# ModuleCarrier-ISM4334X-M4G-L44.net
KiCad netlist of a schematic drawn in EAGLE
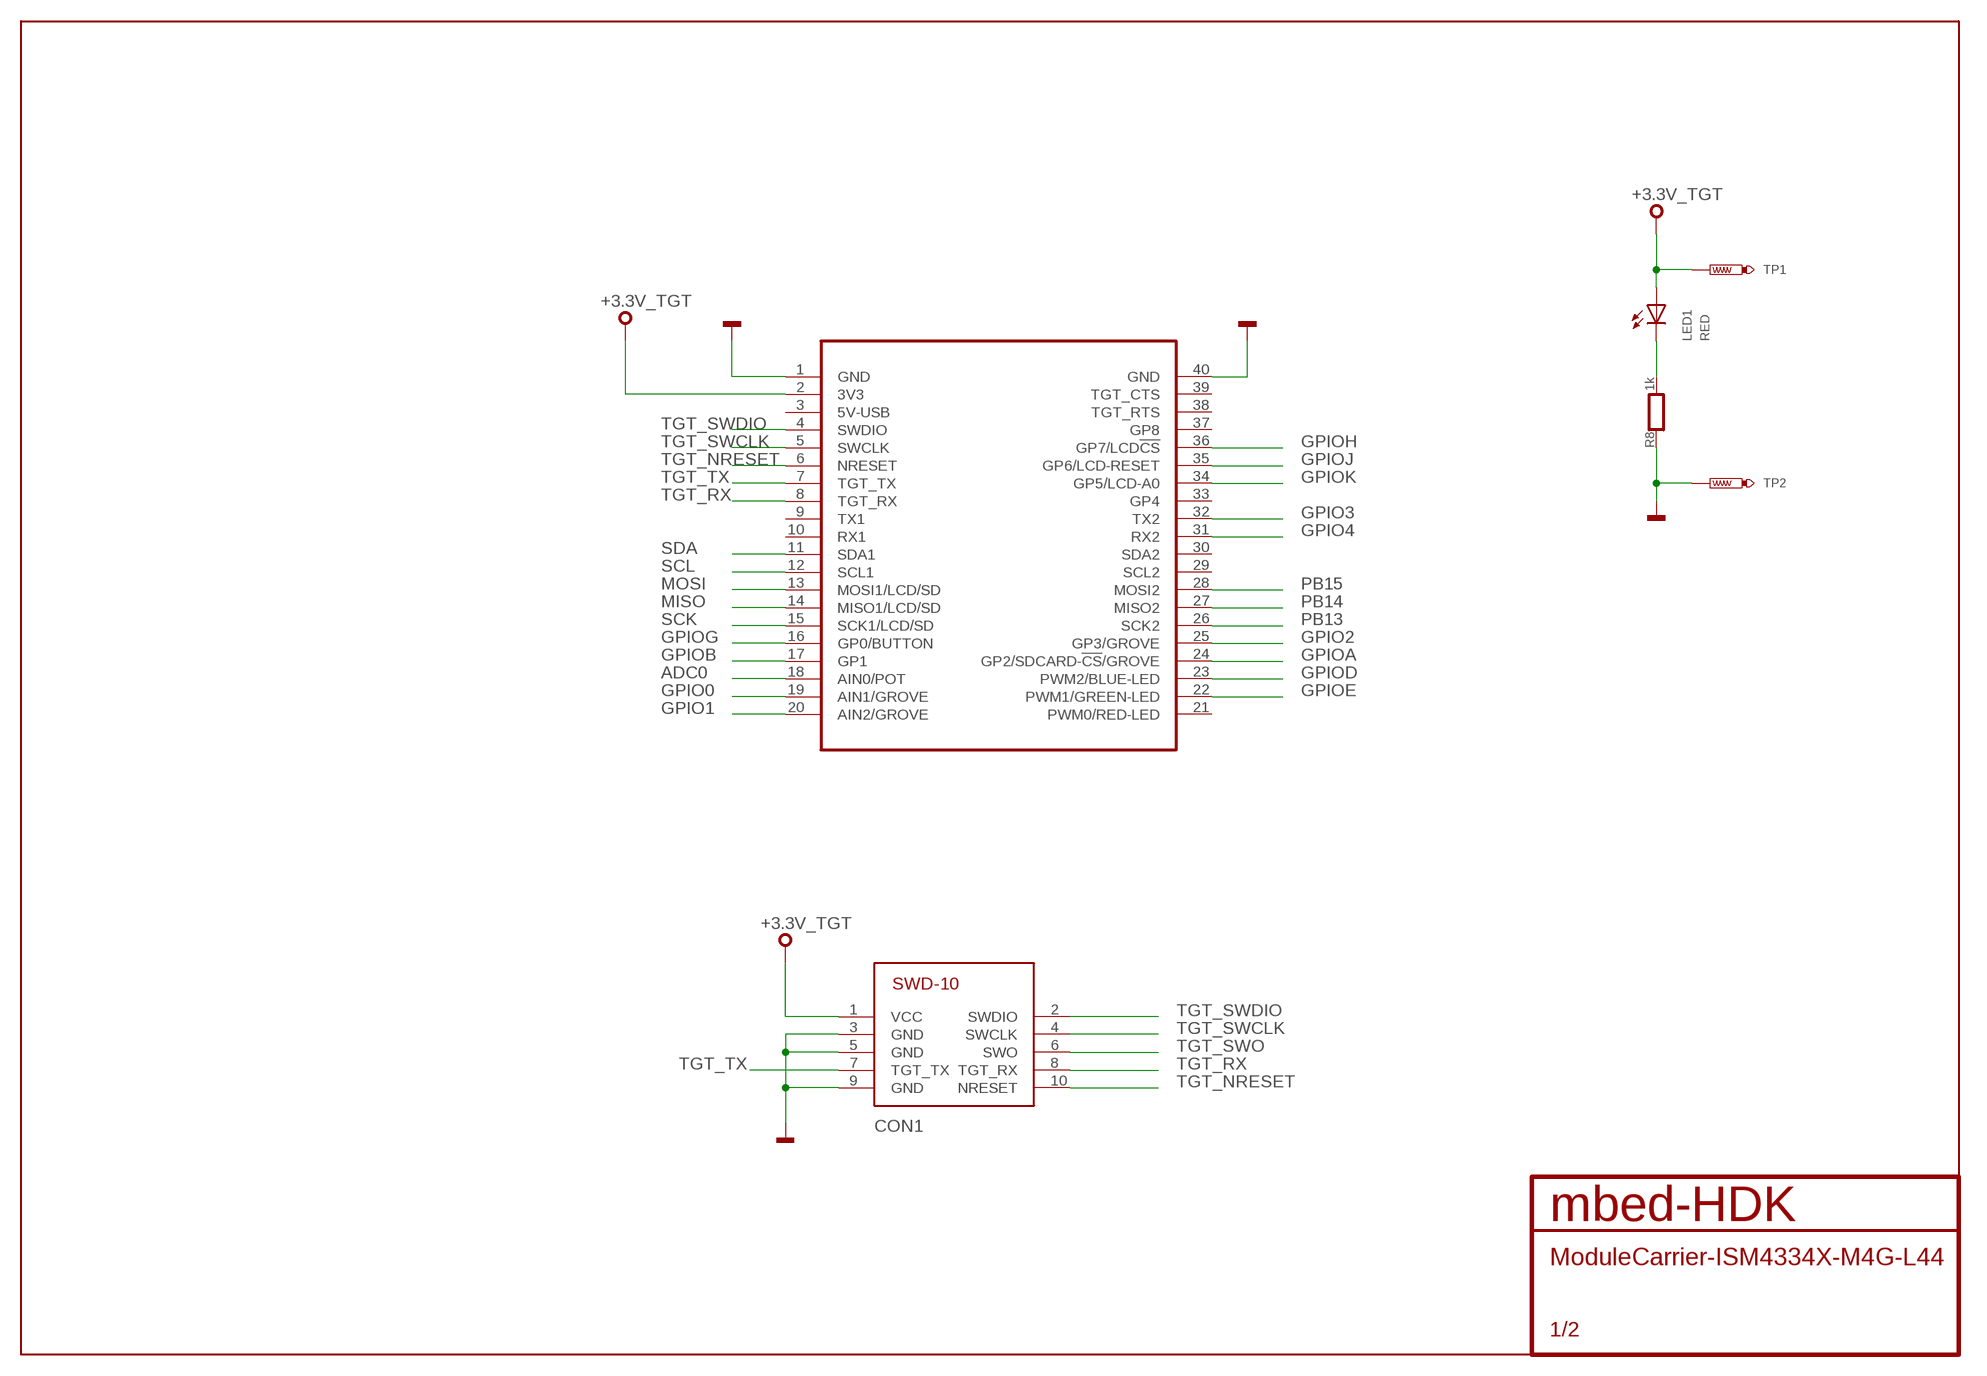
[diagram p0: schematic, sheet 1]
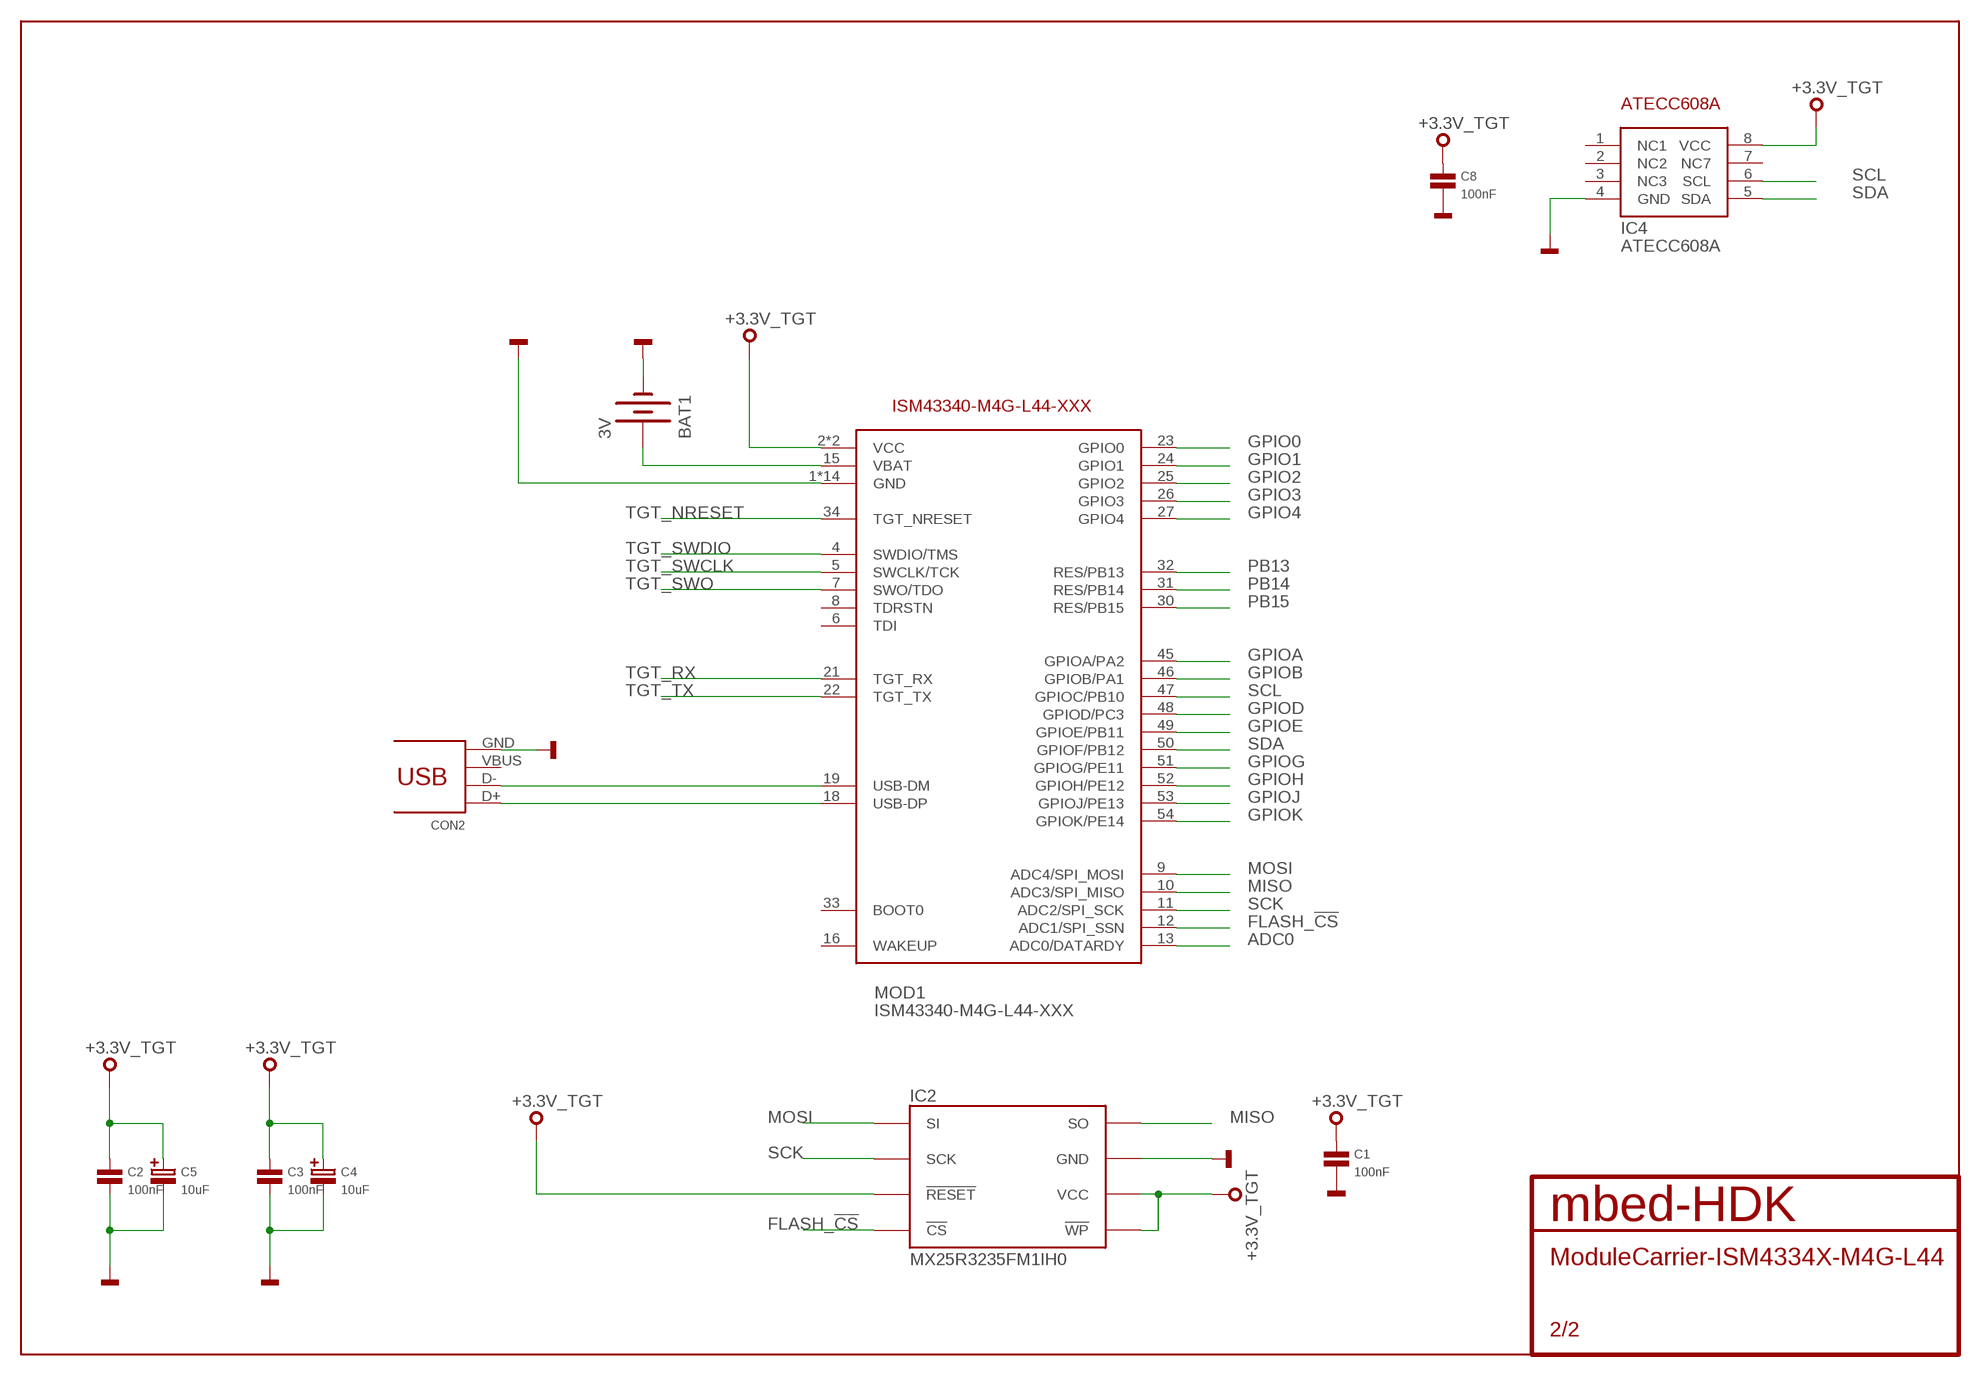
[diagram p1: schematic, sheet 2]

(export (version "E")
  (design (tool "Eeschema 10.0.6"))
  (components
    (comp (ref "BAT1")
      (value "3V")
      (footprint "eagle-import:BATTCON_12MM")
      (libsource (lib "eagle-import") (part "BATTERY12MM"))
    )
    (comp (ref "C1")
      (value "100nF")
      (footprint "eagle-import:0603")
      (libsource (lib "eagle-import") (part "CAPACITOR0603"))
    )
    (comp (ref "C2")
      (value "100nF")
      (footprint "eagle-import:0603")
      (libsource (lib "eagle-import") (part "CAPACITOR0603"))
    )
    (comp (ref "C3")
      (value "100nF")
      (footprint "eagle-import:0603")
      (libsource (lib "eagle-import") (part "CAPACITOR0603"))
    )
    (comp (ref "C4")
      (value "10uF")
      (footprint "eagle-import:SMC_B")
      (fields (field (name "MF") "Kemet"))
      (libsource (lib "eagle-import") (part "CAPACITOR-POLARISEDB"))
    )
    (comp (ref "C5")
      (value "10uF")
      (footprint "eagle-import:SMC_B")
      (fields (field (name "MF") "Kemet"))
      (libsource (lib "eagle-import") (part "CAPACITOR-POLARISEDB"))
    )
    (comp (ref "C8")
      (value "100nF")
      (footprint "eagle-import:0603")
      (libsource (lib "eagle-import") (part "CAPACITOR0603"))
    )
    (comp (ref "CON2")
      (value "10033526-N3212MLF")
      (footprint "eagle-import:USB-MINI-B-H")
      (fields (field (name "MF") "Amphenol FCI"))
      (libsource (lib "eagle-import") (part "10033526-N3212MLF"))
    )
    (comp (ref "IC2")
      (value "MX25R3235FM1IH0")
      (footprint "eagle-import:SO8")
      (fields (field (name "MF") "Macronix"))
      (libsource (lib "eagle-import") (part "MX25R3235FM1IH0"))
    )
    (comp (ref "IC4")
      (value "ATECC608A")
      (footprint "eagle-import:SO8")
      (libsource (lib "eagle-import") (part "ATECC608A"))
    )
    (comp (ref "MOD1")
      (value "ISM43340-M4G-L44-XXX")
      (footprint "eagle-import:ISM43340-M4G-L44-XXX")
      (libsource (lib "eagle-import") (part "ISM43340-M4G-L44-XXX"))
    )
    (comp (ref "CON1")
      (value "SWD-10/TC2050_SMD")
      (footprint "eagle-import:FTSH-105-02")
      (libsource (lib "eagle-import") (part "SWD-10/TC2050_SMD"))
    )
    (comp (ref "LED1")
      (value "RED")
      (footprint "eagle-import:CHIPLED_0603")
      (fields (field (name "MF") "Wurth Electronics Inc"))
      (libsource (lib "eagle-import") (part "SMD_LED0603"))
    )
    (comp (ref "MOD2")
      (value "MODULE_DAUGHTER")
      (footprint "eagle-import:MODULE_DAUGHTER")
      (libsource (lib "eagle-import") (part "MODULE_DAUGHTER"))
    )
    (comp (ref "R8")
      (value "1k")
      (footprint "eagle-import:0603")
      (libsource (lib "eagle-import") (part "RESISTOR0603"))
    )
    (comp (ref "TP1")
      (value "TEST-POINT-50R-PTH")
      (footprint "eagle-import:TP50-PTH")
      (libsource (lib "eagle-import") (part "TEST-POINT-50R-PTH"))
    )
    (comp (ref "TP2")
      (value "TEST-POINT-50R-PTH")
      (footprint "eagle-import:TP50-PTH")
      (libsource (lib "eagle-import") (part "TEST-POINT-50R-PTH"))
    )
  )
  (nets
    (net (code "1") (name "+3.3V_TGT") (class "Default")
      (node (ref "C1") (pin "1") (pinfunction "P$1_1") (pintype "passive"))
      (node (ref "C2") (pin "1") (pinfunction "P$1_1") (pintype "passive"))
      (node (ref "C3") (pin "1") (pinfunction "P$1_1") (pintype "passive"))
      (node (ref "C4") (pin "+") (pinfunction "+_+") (pintype "passive"))
      (node (ref "C5") (pin "+") (pinfunction "+_+") (pintype "passive"))
      (node (ref "C8") (pin "1") (pinfunction "P$1_1") (pintype "passive"))
      (node (ref "CON1") (pin "1") (pinfunction "VCC_1") (pintype "bidirectional"))
      (node (ref "IC2") (pin "3") (pinfunction "~{WP}_3") (pintype "bidirectional"))
      (node (ref "IC2") (pin "7") (pinfunction "~{RESET}_7") (pintype "bidirectional"))
      (node (ref "IC2") (pin "8") (pinfunction "VCC_8") (pintype "bidirectional"))
      (node (ref "IC4") (pin "8") (pinfunction "VCC_8") (pintype "bidirectional"))
      (node (ref "LED1") (pin "A") (pinfunction "A_A") (pintype "passive"))
      (node (ref "MOD1") (pin "14") (pinfunction "VCC_14") (pintype "bidirectional"))
      (node (ref "MOD1") (pin "2") (pinfunction "VCC_2") (pintype "bidirectional"))
      (node (ref "MOD2") (pin "2") (pinfunction "3V3_2") (pintype "bidirectional"))
      (node (ref "TP1") (pin "TP") (pinfunction "TP_TP") (pintype "input"))
    )
    (net (code "2") (name "ADC0") (class "Default")
      (node (ref "MOD1") (pin "13") (pinfunction "ADC0/DATARDY_13") (pintype "bidirectional"))
      (node (ref "MOD2") (pin "18") (pinfunction "AIN0/POT_18") (pintype "bidirectional"))
    )
    (net (code "3") (name "FLASH_~{CS}") (class "Default")
      (node (ref "IC2") (pin "1") (pinfunction "~{CS}_1") (pintype "bidirectional"))
      (node (ref "MOD1") (pin "12") (pinfunction "ADC1/SPI_SSN_12") (pintype "bidirectional"))
    )
    (net (code "4") (name "GND") (class "Default")
      (node (ref "BAT1") (pin "GND") (pinfunction "-_GND") (pintype "power_in"))
      (node (ref "C1") (pin "2") (pinfunction "P$2_2") (pintype "passive"))
      (node (ref "C2") (pin "2") (pinfunction "P$2_2") (pintype "passive"))
      (node (ref "C3") (pin "2") (pinfunction "P$2_2") (pintype "passive"))
      (node (ref "C4") (pin "-") (pinfunction "-_-") (pintype "passive"))
      (node (ref "C5") (pin "-") (pinfunction "-_-") (pintype "passive"))
      (node (ref "C8") (pin "2") (pinfunction "P$2_2") (pintype "passive"))
      (node (ref "CON1") (pin "3") (pinfunction "GND_3") (pintype "bidirectional"))
      (node (ref "CON1") (pin "5") (pinfunction "GND_5") (pintype "bidirectional"))
      (node (ref "CON1") (pin "9") (pinfunction "GND_9") (pintype "bidirectional"))
      (node (ref "CON2") (pin "GND") (pinfunction "GND_GND") (pintype "bidirectional"))
      (node (ref "IC2") (pin "4") (pinfunction "GND_4") (pintype "bidirectional"))
      (node (ref "IC4") (pin "4") (pinfunction "GND_4") (pintype "bidirectional"))
      (node (ref "MOD1") (pin "1") (pinfunction "GND_1") (pintype "bidirectional"))
      (node (ref "MOD1") (pin "17") (pinfunction "GND_17") (pintype "bidirectional"))
      (node (ref "MOD1") (pin "20") (pinfunction "GND_20") (pintype "bidirectional"))
      (node (ref "MOD1") (pin "3") (pinfunction "GND_3") (pintype "bidirectional"))
      (node (ref "MOD1") (pin "35") (pinfunction "GND_35") (pintype "bidirectional"))
      (node (ref "MOD1") (pin "36") (pinfunction "GND_36") (pintype "bidirectional"))
      (node (ref "MOD1") (pin "37") (pinfunction "GND_37") (pintype "bidirectional"))
      (node (ref "MOD1") (pin "38") (pinfunction "GND_38") (pintype "bidirectional"))
      (node (ref "MOD1") (pin "39") (pinfunction "GND_39") (pintype "bidirectional"))
      (node (ref "MOD1") (pin "40") (pinfunction "GND_40") (pintype "bidirectional"))
      (node (ref "MOD1") (pin "41") (pinfunction "GND_41") (pintype "bidirectional"))
      (node (ref "MOD1") (pin "42") (pinfunction "GND_42") (pintype "bidirectional"))
      (node (ref "MOD1") (pin "43") (pinfunction "GND_43") (pintype "bidirectional"))
      (node (ref "MOD1") (pin "44") (pinfunction "GND_44") (pintype "bidirectional"))
      (node (ref "MOD2") (pin "1") (pinfunction "GND_1") (pintype "bidirectional"))
      (node (ref "MOD2") (pin "40") (pinfunction "GND_40") (pintype "bidirectional"))
      (node (ref "R8") (pin "1") (pinfunction "P$1_1") (pintype "passive"))
      (node (ref "TP2") (pin "TP") (pinfunction "TP_TP") (pintype "input"))
    )
    (net (code "5") (name "GPIO0") (class "Default")
      (node (ref "MOD1") (pin "23") (pinfunction "GPIO0_23") (pintype "bidirectional"))
      (node (ref "MOD2") (pin "19") (pinfunction "AIN1/GROVE_19") (pintype "bidirectional"))
    )
    (net (code "6") (name "GPIO1") (class "Default")
      (node (ref "MOD1") (pin "24") (pinfunction "GPIO1_24") (pintype "bidirectional"))
      (node (ref "MOD2") (pin "20") (pinfunction "AIN2/GROVE_20") (pintype "bidirectional"))
    )
    (net (code "7") (name "GPIO2") (class "Default")
      (node (ref "MOD1") (pin "25") (pinfunction "GPIO2_25") (pintype "bidirectional"))
      (node (ref "MOD2") (pin "25") (pinfunction "GP3/GROVE_25") (pintype "bidirectional"))
    )
    (net (code "8") (name "GPIO3") (class "Default")
      (node (ref "MOD1") (pin "26") (pinfunction "GPIO3_26") (pintype "bidirectional"))
      (node (ref "MOD2") (pin "32") (pinfunction "TX2_32") (pintype "bidirectional"))
    )
    (net (code "9") (name "GPIO4") (class "Default")
      (node (ref "MOD1") (pin "27") (pinfunction "GPIO4_27") (pintype "bidirectional"))
      (node (ref "MOD2") (pin "31") (pinfunction "RX2_31") (pintype "bidirectional"))
    )
    (net (code "10") (name "GPIOA") (class "Default")
      (node (ref "MOD1") (pin "45") (pinfunction "GPIOA/PA2_45") (pintype "bidirectional"))
      (node (ref "MOD2") (pin "24") (pinfunction "GP2/SDCARD-~{CS}/GROVE_24") (pintype "bidirectional"))
    )
    (net (code "11") (name "GPIOB") (class "Default")
      (node (ref "MOD1") (pin "46") (pinfunction "GPIOB/PA1_46") (pintype "bidirectional"))
      (node (ref "MOD2") (pin "17") (pinfunction "GP1_17") (pintype "bidirectional"))
    )
    (net (code "12") (name "GPIOD") (class "Default")
      (node (ref "MOD1") (pin "48") (pinfunction "GPIOD/PC3_48") (pintype "bidirectional"))
      (node (ref "MOD2") (pin "23") (pinfunction "PWM2/BLUE-LED_23") (pintype "bidirectional"))
    )
    (net (code "13") (name "GPIOE") (class "Default")
      (node (ref "MOD1") (pin "49") (pinfunction "GPIOE/PB11_49") (pintype "bidirectional"))
      (node (ref "MOD2") (pin "22") (pinfunction "PWM1/GREEN-LED_22") (pintype "bidirectional"))
    )
    (net (code "14") (name "GPIOG") (class "Default")
      (node (ref "MOD1") (pin "51") (pinfunction "GPIOG/PE11_51") (pintype "bidirectional"))
      (node (ref "MOD2") (pin "16") (pinfunction "GP0/BUTTON_16") (pintype "bidirectional"))
    )
    (net (code "15") (name "GPIOH") (class "Default")
      (node (ref "MOD1") (pin "52") (pinfunction "GPIOH/PE12_52") (pintype "bidirectional"))
      (node (ref "MOD2") (pin "36") (pinfunction "GP7/LCD~{CS}_36") (pintype "bidirectional"))
    )
    (net (code "16") (name "GPIOJ") (class "Default")
      (node (ref "MOD1") (pin "53") (pinfunction "GPIOJ/PE13_53") (pintype "bidirectional"))
      (node (ref "MOD2") (pin "35") (pinfunction "GP6/LCD-RESET_35") (pintype "bidirectional"))
    )
    (net (code "17") (name "GPIOK") (class "Default")
      (node (ref "MOD1") (pin "54") (pinfunction "GPIOK/PE14_54") (pintype "bidirectional"))
      (node (ref "MOD2") (pin "34") (pinfunction "GP5/LCD-A0_34") (pintype "bidirectional"))
    )
    (net (code "18") (name "MISO") (class "Default")
      (node (ref "IC2") (pin "2") (pinfunction "SO_2") (pintype "bidirectional"))
      (node (ref "MOD1") (pin "10") (pinfunction "ADC3/SPI_MISO_10") (pintype "bidirectional"))
      (node (ref "MOD2") (pin "14") (pinfunction "MISO1/LCD/SD_14") (pintype "bidirectional"))
    )
    (net (code "19") (name "MOSI") (class "Default")
      (node (ref "IC2") (pin "5") (pinfunction "SI_5") (pintype "bidirectional"))
      (node (ref "MOD1") (pin "9") (pinfunction "ADC4/SPI_MOSI_9") (pintype "bidirectional"))
      (node (ref "MOD2") (pin "13") (pinfunction "MOSI1/LCD/SD_13") (pintype "bidirectional"))
    )
    (net (code "20") (name "Net-(BAT1-+)") (class "Default")
      (node (ref "BAT1") (pin "PWR@1") (pinfunction "+_PWR@1") (pintype "power_in"))
      (node (ref "MOD1") (pin "15") (pinfunction "VBAT_15") (pintype "bidirectional"))
    )
    (net (code "21") (name "Net-(MOD1-USB-DM)") (class "Default")
      (node (ref "CON2") (pin "D-") (pinfunction "D-_D-") (pintype "bidirectional"))
      (node (ref "MOD1") (pin "19") (pinfunction "USB-DM_19") (pintype "bidirectional"))
    )
    (net (code "22") (name "Net-(MOD1-USB-DP)") (class "Default")
      (node (ref "CON2") (pin "D+") (pinfunction "D+_D+") (pintype "bidirectional"))
      (node (ref "MOD1") (pin "18") (pinfunction "USB-DP_18") (pintype "bidirectional"))
    )
    (net (code "23") (name "Net-(R8-P$2)") (class "Default")
      (node (ref "LED1") (pin "C") (pinfunction "C_C") (pintype "passive"))
      (node (ref "R8") (pin "2") (pinfunction "P$2_2") (pintype "passive"))
    )
    (net (code "24") (name "PB13") (class "Default")
      (node (ref "MOD1") (pin "32") (pinfunction "RES/PB13_32") (pintype "bidirectional"))
      (node (ref "MOD2") (pin "26") (pinfunction "SCK2_26") (pintype "bidirectional"))
    )
    (net (code "25") (name "PB14") (class "Default")
      (node (ref "MOD1") (pin "31") (pinfunction "RES/PB14_31") (pintype "bidirectional"))
      (node (ref "MOD2") (pin "27") (pinfunction "MISO2_27") (pintype "bidirectional"))
    )
    (net (code "26") (name "PB15") (class "Default")
      (node (ref "MOD1") (pin "30") (pinfunction "RES/PB15_30") (pintype "bidirectional"))
      (node (ref "MOD2") (pin "28") (pinfunction "MOSI2_28") (pintype "bidirectional"))
    )
    (net (code "27") (name "SCK") (class "Default")
      (node (ref "IC2") (pin "6") (pinfunction "SCK_6") (pintype "bidirectional"))
      (node (ref "MOD1") (pin "11") (pinfunction "ADC2/SPI_SCK_11") (pintype "bidirectional"))
      (node (ref "MOD2") (pin "15") (pinfunction "SCK1/LCD/SD_15") (pintype "bidirectional"))
    )
    (net (code "28") (name "SCL") (class "Default")
      (node (ref "IC4") (pin "6") (pinfunction "SCL_6") (pintype "bidirectional"))
      (node (ref "MOD1") (pin "47") (pinfunction "GPIOC/PB10_47") (pintype "bidirectional"))
      (node (ref "MOD2") (pin "12") (pinfunction "SCL1_12") (pintype "bidirectional"))
    )
    (net (code "29") (name "SDA") (class "Default")
      (node (ref "IC4") (pin "5") (pinfunction "SDA_5") (pintype "bidirectional"))
      (node (ref "MOD1") (pin "50") (pinfunction "GPIOF/PB12_50") (pintype "bidirectional"))
      (node (ref "MOD2") (pin "11") (pinfunction "SDA1_11") (pintype "bidirectional"))
    )
    (net (code "30") (name "TGT_NRESET") (class "Default")
      (node (ref "CON1") (pin "10") (pinfunction "NRESET_10") (pintype "bidirectional"))
      (node (ref "MOD1") (pin "34") (pinfunction "TGT_NRESET_34") (pintype "bidirectional"))
      (node (ref "MOD2") (pin "6") (pinfunction "NRESET_6") (pintype "bidirectional"))
    )
    (net (code "31") (name "TGT_RX") (class "Default")
      (node (ref "CON1") (pin "8") (pinfunction "TGT_RX_8") (pintype "bidirectional"))
      (node (ref "MOD1") (pin "21") (pinfunction "TGT_RX_21") (pintype "bidirectional"))
      (node (ref "MOD2") (pin "8") (pinfunction "TGT_RX_8") (pintype "bidirectional"))
    )
    (net (code "32") (name "TGT_SWCLK") (class "Default")
      (node (ref "CON1") (pin "4") (pinfunction "SWCLK_4") (pintype "bidirectional"))
      (node (ref "MOD1") (pin "5") (pinfunction "SWCLK/TCK_5") (pintype "bidirectional"))
      (node (ref "MOD2") (pin "5") (pinfunction "SWCLK_5") (pintype "bidirectional"))
    )
    (net (code "33") (name "TGT_SWDIO") (class "Default")
      (node (ref "CON1") (pin "2") (pinfunction "SWDIO_2") (pintype "bidirectional"))
      (node (ref "MOD1") (pin "4") (pinfunction "SWDIO/TMS_4") (pintype "bidirectional"))
      (node (ref "MOD2") (pin "4") (pinfunction "SWDIO_4") (pintype "bidirectional"))
    )
    (net (code "34") (name "TGT_SWO") (class "Default")
      (node (ref "CON1") (pin "6") (pinfunction "SWO_6") (pintype "bidirectional"))
      (node (ref "MOD1") (pin "7") (pinfunction "SWO/TDO_7") (pintype "bidirectional"))
    )
    (net (code "35") (name "TGT_TX") (class "Default")
      (node (ref "CON1") (pin "7") (pinfunction "TGT_TX_7") (pintype "bidirectional"))
      (node (ref "MOD1") (pin "22") (pinfunction "TGT_TX_22") (pintype "bidirectional"))
      (node (ref "MOD2") (pin "7") (pinfunction "TGT_TX_7") (pintype "bidirectional"))
    )
    (net (code "36") (name "unconnected-(CON2-PadVBUS)") (class "Default")
      (node (ref "CON2") (pin "VBUS") (pinfunction "VBUS_VBUS") (pintype "bidirectional"))
    )
    (net (code "37") (name "unconnected-(IC4-NC1-Pad1)") (class "Default")
      (node (ref "IC4") (pin "1") (pinfunction "NC1_1") (pintype "bidirectional"))
    )
    (net (code "38") (name "unconnected-(IC4-NC2-Pad2)") (class "Default")
      (node (ref "IC4") (pin "2") (pinfunction "NC2_2") (pintype "bidirectional"))
    )
    (net (code "39") (name "unconnected-(IC4-NC3-Pad3)") (class "Default")
      (node (ref "IC4") (pin "3") (pinfunction "NC3_3") (pintype "bidirectional"))
    )
    (net (code "40") (name "unconnected-(IC4-NC7-Pad7)") (class "Default")
      (node (ref "IC4") (pin "7") (pinfunction "NC7_7") (pintype "bidirectional"))
    )
    (net (code "41") (name "unconnected-(MOD1-BOOT0-Pad33)") (class "Default")
      (node (ref "MOD1") (pin "33") (pinfunction "BOOT0_33") (pintype "bidirectional"))
    )
    (net (code "42") (name "unconnected-(MOD1-TDI-Pad6)") (class "Default")
      (node (ref "MOD1") (pin "6") (pinfunction "TDI_6") (pintype "bidirectional"))
    )
    (net (code "43") (name "unconnected-(MOD1-TDRSTN-Pad8)") (class "Default")
      (node (ref "MOD1") (pin "8") (pinfunction "TDRSTN_8") (pintype "bidirectional"))
    )
    (net (code "44") (name "unconnected-(MOD1-WAKEUP-Pad16)") (class "Default")
      (node (ref "MOD1") (pin "16") (pinfunction "WAKEUP_16") (pintype "bidirectional"))
    )
    (net (code "45") (name "unconnected-(MOD2-5V-USB-Pad3)") (class "Default")
      (node (ref "MOD2") (pin "3") (pinfunction "5V-USB_3") (pintype "bidirectional"))
    )
    (net (code "46") (name "unconnected-(MOD2-GP4-Pad33)") (class "Default")
      (node (ref "MOD2") (pin "33") (pinfunction "GP4_33") (pintype "bidirectional"))
    )
    (net (code "47") (name "unconnected-(MOD2-GP8-Pad37)") (class "Default")
      (node (ref "MOD2") (pin "37") (pinfunction "GP8_37") (pintype "bidirectional"))
    )
    (net (code "48") (name "unconnected-(MOD2-PWM0{slash}RED-LED-Pad21)") (class "Default")
      (node (ref "MOD2") (pin "21") (pinfunction "PWM0/RED-LED_21") (pintype "bidirectional"))
    )
    (net (code "49") (name "unconnected-(MOD2-RX1-Pad10)") (class "Default")
      (node (ref "MOD2") (pin "10") (pinfunction "RX1_10") (pintype "bidirectional"))
    )
    (net (code "50") (name "unconnected-(MOD2-SCL2-Pad29)") (class "Default")
      (node (ref "MOD2") (pin "29") (pinfunction "SCL2_29") (pintype "bidirectional"))
    )
    (net (code "51") (name "unconnected-(MOD2-SDA2-Pad30)") (class "Default")
      (node (ref "MOD2") (pin "30") (pinfunction "SDA2_30") (pintype "bidirectional"))
    )
    (net (code "52") (name "unconnected-(MOD2-TGT_CTS-Pad39)") (class "Default")
      (node (ref "MOD2") (pin "39") (pinfunction "TGT_CTS_39") (pintype "bidirectional"))
    )
    (net (code "53") (name "unconnected-(MOD2-TGT_RTS-Pad38)") (class "Default")
      (node (ref "MOD2") (pin "38") (pinfunction "TGT_RTS_38") (pintype "bidirectional"))
    )
    (net (code "54") (name "unconnected-(MOD2-TX1-Pad9)") (class "Default")
      (node (ref "MOD2") (pin "9") (pinfunction "TX1_9") (pintype "bidirectional"))
    )
  )
)
